# HRT_PDB_17-18_schem.net
KiCad netlist of a schematic drawn in EAGLE
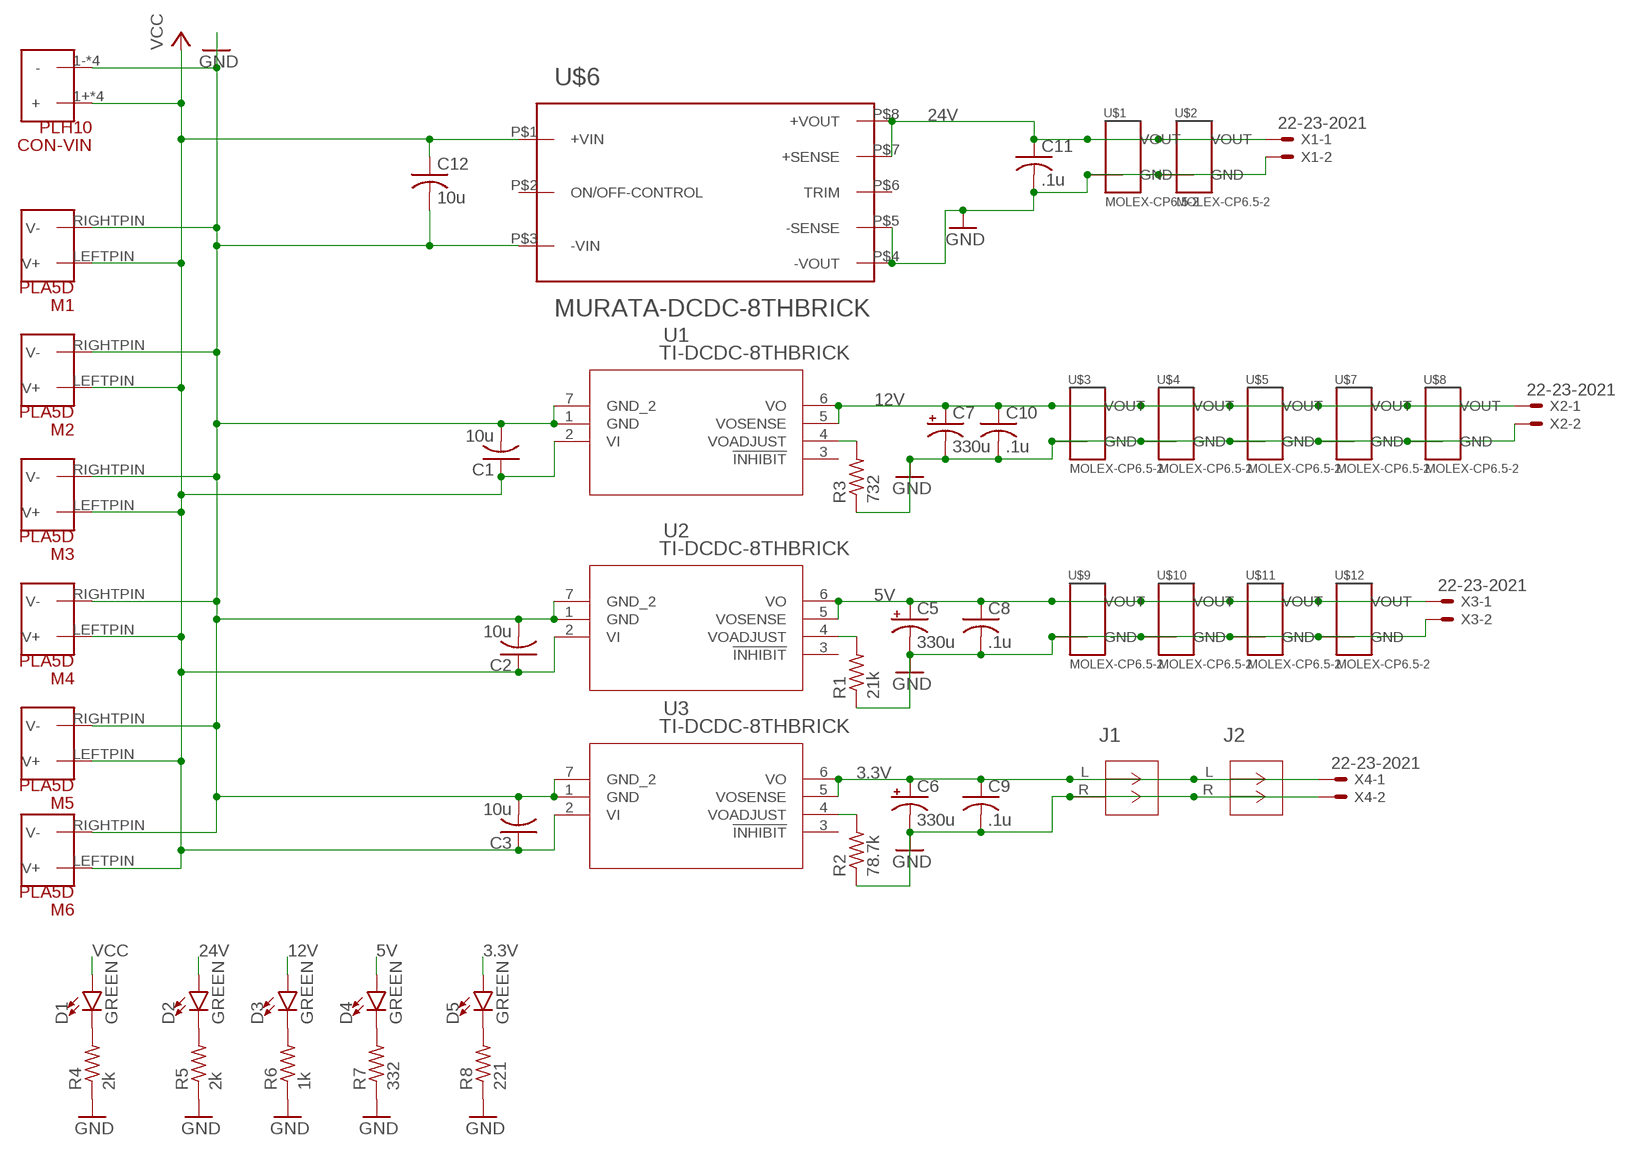
[diagram p0: schematic, sheet 1]

(export (version "E")
  (design (tool "Eeschema 10.0.6"))
  (components
    (comp (ref "C1")
      (value "10u")
      (footprint "eagle-import:C1210")
      (libsource (lib "eagle-import") (part "C-USC1210"))
    )
    (comp (ref "C2")
      (value "10u")
      (footprint "eagle-import:C1210")
      (libsource (lib "eagle-import") (part "C-USC1210"))
    )
    (comp (ref "C3")
      (value "10u")
      (footprint "eagle-import:C1210")
      (libsource (lib "eagle-import") (part "C-USC1210"))
    )
    (comp (ref "C5")
      (value "330u")
      (footprint "eagle-import:E5-10,5")
      (libsource (lib "eagle-import") (part "CPOL-USE5-10.5"))
    )
    (comp (ref "C6")
      (value "330u")
      (footprint "eagle-import:E5-10,5")
      (libsource (lib "eagle-import") (part "CPOL-USE5-10.5"))
    )
    (comp (ref "C7")
      (value "330u")
      (footprint "eagle-import:E5-10,5")
      (libsource (lib "eagle-import") (part "CPOL-USE5-10.5"))
    )
    (comp (ref "C8")
      (value ".1u")
      (footprint "eagle-import:C0603")
      (libsource (lib "eagle-import") (part "C-USC0603"))
    )
    (comp (ref "C9")
      (value ".1u")
      (footprint "eagle-import:C0603")
      (libsource (lib "eagle-import") (part "C-USC0603"))
    )
    (comp (ref "C10")
      (value ".1u")
      (footprint "eagle-import:C0603")
      (libsource (lib "eagle-import") (part "C-USC0603"))
    )
    (comp (ref "C11")
      (value ".1u")
      (footprint "eagle-import:C0603")
      (libsource (lib "eagle-import") (part "C-USC0603"))
    )
    (comp (ref "C12")
      (value "10u")
      (footprint "eagle-import:C1210")
      (libsource (lib "eagle-import") (part "C-USC1210"))
    )
    (comp (ref "CON-VIN")
      (value "PLH10")
      (footprint "eagle-import:PLH10PCKG")
      (libsource (lib "eagle-import") (part "PLH10"))
    )
    (comp (ref "D1")
      (value "GREEN")
      (footprint "eagle-import:LED-0603")
      (libsource (lib "eagle-import") (part "LED-GREEN0603"))
    )
    (comp (ref "D2")
      (value "GREEN")
      (footprint "eagle-import:LED-0603")
      (libsource (lib "eagle-import") (part "LED-GREEN0603"))
    )
    (comp (ref "D3")
      (value "GREEN")
      (footprint "eagle-import:LED-0603")
      (libsource (lib "eagle-import") (part "LED-GREEN0603"))
    )
    (comp (ref "D4")
      (value "GREEN")
      (footprint "eagle-import:LED-0603")
      (libsource (lib "eagle-import") (part "LED-GREEN0603"))
    )
    (comp (ref "D5")
      (value "GREEN")
      (footprint "eagle-import:LED-0603")
      (libsource (lib "eagle-import") (part "LED-GREEN0603"))
    )
    (comp (ref "J1")
      (value "TE-TERM-BLOCK")
      (footprint "eagle-import:TE-TERM-BLOCK")
      (fields (field (name "MANUFACTURER_PART_NUMBER") "2828342"))
      (libsource (lib "eagle-import") (part "TE-TERM-BLOCK"))
    )
    (comp (ref "J2")
      (value "TE-TERM-BLOCK")
      (footprint "eagle-import:TE-TERM-BLOCK")
      (fields (field (name "MANUFACTURER_PART_NUMBER") "2828342"))
      (libsource (lib "eagle-import") (part "TE-TERM-BLOCK"))
    )
    (comp (ref "M1")
      (value "PLA5D")
      (footprint "eagle-import:PLA5PACK")
      (libsource (lib "eagle-import") (part "PLA5D"))
    )
    (comp (ref "M2")
      (value "PLA5D")
      (footprint "eagle-import:PLA5PACK")
      (libsource (lib "eagle-import") (part "PLA5D"))
    )
    (comp (ref "M3")
      (value "PLA5D")
      (footprint "eagle-import:PLA5PACK")
      (libsource (lib "eagle-import") (part "PLA5D"))
    )
    (comp (ref "M4")
      (value "PLA5D")
      (footprint "eagle-import:PLA5PACK")
      (libsource (lib "eagle-import") (part "PLA5D"))
    )
    (comp (ref "M5")
      (value "PLA5D")
      (footprint "eagle-import:PLA5PACK")
      (libsource (lib "eagle-import") (part "PLA5D"))
    )
    (comp (ref "M6")
      (value "PLA5D")
      (footprint "eagle-import:PLA5PACK")
      (libsource (lib "eagle-import") (part "PLA5D"))
    )
    (comp (ref "R1")
      (value "21k")
      (footprint "eagle-import:R0603")
      (libsource (lib "eagle-import") (part "R-US_R0603"))
    )
    (comp (ref "R2")
      (value "78.7k")
      (footprint "eagle-import:R0603")
      (libsource (lib "eagle-import") (part "R-US_R0603"))
    )
    (comp (ref "R3")
      (value "732")
      (footprint "eagle-import:R0603")
      (libsource (lib "eagle-import") (part "R-US_R0603"))
    )
    (comp (ref "R4")
      (value "2k")
      (footprint "eagle-import:R0805")
      (libsource (lib "eagle-import") (part "R-US_R0805"))
    )
    (comp (ref "R5")
      (value "2k")
      (footprint "eagle-import:R0805")
      (libsource (lib "eagle-import") (part "R-US_R0805"))
    )
    (comp (ref "R6")
      (value "1k")
      (footprint "eagle-import:R0805")
      (libsource (lib "eagle-import") (part "R-US_R0805"))
    )
    (comp (ref "R7")
      (value "332")
      (footprint "eagle-import:R0805")
      (libsource (lib "eagle-import") (part "R-US_R0805"))
    )
    (comp (ref "R8")
      (value "221")
      (footprint "eagle-import:R0805")
      (libsource (lib "eagle-import") (part "R-US_R0805"))
    )
    (comp (ref "U$1")
      (value "MOLEX-CP6.5-2")
      (footprint "eagle-import:151048-X2XX")
      (libsource (lib "eagle-import") (part "MOLEX-CP6.5-2"))
    )
    (comp (ref "U$2")
      (value "MOLEX-CP6.5-2")
      (footprint "eagle-import:151048-X2XX")
      (libsource (lib "eagle-import") (part "MOLEX-CP6.5-2"))
    )
    (comp (ref "U$3")
      (value "MOLEX-CP6.5-2")
      (footprint "eagle-import:151048-X2XX")
      (libsource (lib "eagle-import") (part "MOLEX-CP6.5-2"))
    )
    (comp (ref "U$4")
      (value "MOLEX-CP6.5-2")
      (footprint "eagle-import:151048-X2XX")
      (libsource (lib "eagle-import") (part "MOLEX-CP6.5-2"))
    )
    (comp (ref "U$5")
      (value "MOLEX-CP6.5-2")
      (footprint "eagle-import:151048-X2XX")
      (libsource (lib "eagle-import") (part "MOLEX-CP6.5-2"))
    )
    (comp (ref "U$6")
      (value "MURATA-DCDC-8THBRICK")
      (footprint "eagle-import:MURATA-8THBRICK")
      (libsource (lib "eagle-import") (part "MURATA-DCDC-8THBRICK"))
    )
    (comp (ref "U$7")
      (value "MOLEX-CP6.5-2")
      (footprint "eagle-import:151048-X2XX")
      (libsource (lib "eagle-import") (part "MOLEX-CP6.5-2"))
    )
    (comp (ref "U$8")
      (value "MOLEX-CP6.5-2")
      (footprint "eagle-import:151048-X2XX")
      (libsource (lib "eagle-import") (part "MOLEX-CP6.5-2"))
    )
    (comp (ref "U$9")
      (value "MOLEX-CP6.5-2")
      (footprint "eagle-import:151048-X2XX")
      (libsource (lib "eagle-import") (part "MOLEX-CP6.5-2"))
    )
    (comp (ref "U$10")
      (value "MOLEX-CP6.5-2")
      (footprint "eagle-import:151048-X2XX")
      (libsource (lib "eagle-import") (part "MOLEX-CP6.5-2"))
    )
    (comp (ref "U$11")
      (value "MOLEX-CP6.5-2")
      (footprint "eagle-import:151048-X2XX")
      (libsource (lib "eagle-import") (part "MOLEX-CP6.5-2"))
    )
    (comp (ref "U$12")
      (value "MOLEX-CP6.5-2")
      (footprint "eagle-import:151048-X2XX")
      (libsource (lib "eagle-import") (part "MOLEX-CP6.5-2"))
    )
    (comp (ref "U1")
      (value "TI-DCDC-8THBRICK")
      (footprint "eagle-import:TIBRICK")
      (fields (field (name "MANUFACTURER_PART_NUMBER") "PTN78020WAH"))
      (libsource (lib "eagle-import") (part "TI-DCDC-8THBRICK"))
    )
    (comp (ref "U2")
      (value "TI-DCDC-8THBRICK")
      (footprint "eagle-import:TIBRICK")
      (fields (field (name "MANUFACTURER_PART_NUMBER") "PTN78020WAH"))
      (libsource (lib "eagle-import") (part "TI-DCDC-8THBRICK"))
    )
    (comp (ref "U3")
      (value "TI-DCDC-8THBRICK")
      (footprint "eagle-import:TIBRICK")
      (fields (field (name "MANUFACTURER_PART_NUMBER") "PTN78020WAH"))
      (libsource (lib "eagle-import") (part "TI-DCDC-8THBRICK"))
    )
    (comp (ref "X1")
      (value "22-23-2021")
      (footprint "eagle-import:22-23-2021")
      (fields (field (name "MF") "MOLEX"))
      (libsource (lib "eagle-import") (part "22-23-2021"))
    )
    (comp (ref "X2")
      (value "22-23-2021")
      (footprint "eagle-import:22-23-2021")
      (fields (field (name "MF") "MOLEX"))
      (libsource (lib "eagle-import") (part "22-23-2021"))
    )
    (comp (ref "X3")
      (value "22-23-2021")
      (footprint "eagle-import:22-23-2021")
      (fields (field (name "MF") "MOLEX"))
      (libsource (lib "eagle-import") (part "22-23-2021"))
    )
    (comp (ref "X4")
      (value "22-23-2021")
      (footprint "eagle-import:22-23-2021")
      (fields (field (name "MF") "MOLEX"))
      (libsource (lib "eagle-import") (part "22-23-2021"))
    )
  )
  (nets
    (net (code "1") (name "/3.3V") (class "Default")
      (node (ref "C6") (pin "+") (pinfunction "+_+") (pintype "passive"))
      (node (ref "C9") (pin "1") (pinfunction "1_1") (pintype "passive"))
      (node (ref "D5") (pin "A") (pinfunction "A_A") (pintype "passive"))
      (node (ref "J1") (pin "L") (pinfunction "1_L") (pintype "passive"))
      (node (ref "J2") (pin "L") (pinfunction "1_L") (pintype "passive"))
      (node (ref "U3") (pin "5") (pinfunction "VOSENSE_5") (pintype "input"))
      (node (ref "U3") (pin "6") (pinfunction "VO_6") (pintype "input"))
      (node (ref "X4") (pin "1") (pinfunction "S_1") (pintype "passive"))
    )
    (net (code "2") (name "/5V") (class "Default")
      (node (ref "C5") (pin "+") (pinfunction "+_+") (pintype "passive"))
      (node (ref "C8") (pin "1") (pinfunction "1_1") (pintype "passive"))
      (node (ref "D4") (pin "A") (pinfunction "A_A") (pintype "passive"))
      (node (ref "U$10") (pin "VOUT") (pinfunction "VOUT_VOUT") (pintype "bidirectional"))
      (node (ref "U$11") (pin "VOUT") (pinfunction "VOUT_VOUT") (pintype "bidirectional"))
      (node (ref "U$12") (pin "VOUT") (pinfunction "VOUT_VOUT") (pintype "bidirectional"))
      (node (ref "U$9") (pin "VOUT") (pinfunction "VOUT_VOUT") (pintype "bidirectional"))
      (node (ref "U2") (pin "5") (pinfunction "VOSENSE_5") (pintype "input"))
      (node (ref "U2") (pin "6") (pinfunction "VO_6") (pintype "input"))
      (node (ref "X3") (pin "1") (pinfunction "S_1") (pintype "passive"))
    )
    (net (code "3") (name "/12V") (class "Default")
      (node (ref "C10") (pin "1") (pinfunction "1_1") (pintype "passive"))
      (node (ref "C7") (pin "+") (pinfunction "+_+") (pintype "passive"))
      (node (ref "D3") (pin "A") (pinfunction "A_A") (pintype "passive"))
      (node (ref "U$3") (pin "VOUT") (pinfunction "VOUT_VOUT") (pintype "bidirectional"))
      (node (ref "U$4") (pin "VOUT") (pinfunction "VOUT_VOUT") (pintype "bidirectional"))
      (node (ref "U$5") (pin "VOUT") (pinfunction "VOUT_VOUT") (pintype "bidirectional"))
      (node (ref "U$7") (pin "VOUT") (pinfunction "VOUT_VOUT") (pintype "bidirectional"))
      (node (ref "U$8") (pin "VOUT") (pinfunction "VOUT_VOUT") (pintype "bidirectional"))
      (node (ref "U1") (pin "5") (pinfunction "VOSENSE_5") (pintype "input"))
      (node (ref "U1") (pin "6") (pinfunction "VO_6") (pintype "input"))
      (node (ref "X2") (pin "1") (pinfunction "S_1") (pintype "passive"))
    )
    (net (code "4") (name "/24V") (class "Default")
      (node (ref "C11") (pin "1") (pinfunction "1_1") (pintype "passive"))
      (node (ref "D2") (pin "A") (pinfunction "A_A") (pintype "passive"))
      (node (ref "U$1") (pin "VOUT") (pinfunction "VOUT_VOUT") (pintype "bidirectional"))
      (node (ref "U$2") (pin "VOUT") (pinfunction "VOUT_VOUT") (pintype "bidirectional"))
      (node (ref "U$6") (pin "P$7") (pinfunction "+SENSE_P$7") (pintype "bidirectional"))
      (node (ref "U$6") (pin "P$8") (pinfunction "+VOUT_P$8") (pintype "bidirectional"))
      (node (ref "X1") (pin "1") (pinfunction "S_1") (pintype "passive"))
    )
    (net (code "5") (name "GND") (class "Default")
      (node (ref "C1") (pin "2") (pinfunction "2_2") (pintype "passive"))
      (node (ref "C10") (pin "2") (pinfunction "2_2") (pintype "passive"))
      (node (ref "C11") (pin "2") (pinfunction "2_2") (pintype "passive"))
      (node (ref "C12") (pin "2") (pinfunction "2_2") (pintype "passive"))
      (node (ref "C2") (pin "2") (pinfunction "2_2") (pintype "passive"))
      (node (ref "C3") (pin "2") (pinfunction "2_2") (pintype "passive"))
      (node (ref "C5") (pin "-") (pinfunction "-_-") (pintype "passive"))
      (node (ref "C6") (pin "-") (pinfunction "-_-") (pintype "passive"))
      (node (ref "C7") (pin "-") (pinfunction "-_-") (pintype "passive"))
      (node (ref "C8") (pin "2") (pinfunction "2_2") (pintype "passive"))
      (node (ref "C9") (pin "2") (pinfunction "2_2") (pintype "passive"))
      (node (ref "CON-VIN") (pin "1-") (pinfunction "-_1-") (pintype "bidirectional"))
      (node (ref "CON-VIN") (pin "2-") (pinfunction "-_2-") (pintype "bidirectional"))
      (node (ref "CON-VIN") (pin "3-") (pinfunction "-_3-") (pintype "bidirectional"))
      (node (ref "CON-VIN") (pin "4-") (pinfunction "-_4-") (pintype "bidirectional"))
      (node (ref "J1") (pin "R") (pinfunction "2_R") (pintype "passive"))
      (node (ref "J2") (pin "R") (pinfunction "2_R") (pintype "passive"))
      (node (ref "M1") (pin "RIGHTPIN") (pinfunction "V-_RIGHTPIN") (pintype "bidirectional"))
      (node (ref "M2") (pin "RIGHTPIN") (pinfunction "V-_RIGHTPIN") (pintype "bidirectional"))
      (node (ref "M3") (pin "RIGHTPIN") (pinfunction "V-_RIGHTPIN") (pintype "bidirectional"))
      (node (ref "M4") (pin "RIGHTPIN") (pinfunction "V-_RIGHTPIN") (pintype "bidirectional"))
      (node (ref "M5") (pin "RIGHTPIN") (pinfunction "V-_RIGHTPIN") (pintype "bidirectional"))
      (node (ref "M6") (pin "RIGHTPIN") (pinfunction "V-_RIGHTPIN") (pintype "bidirectional"))
      (node (ref "R1") (pin "1") (pinfunction "1_1") (pintype "passive"))
      (node (ref "R2") (pin "1") (pinfunction "1_1") (pintype "passive"))
      (node (ref "R3") (pin "1") (pinfunction "1_1") (pintype "passive"))
      (node (ref "R4") (pin "1") (pinfunction "1_1") (pintype "passive"))
      (node (ref "R5") (pin "1") (pinfunction "1_1") (pintype "passive"))
      (node (ref "R6") (pin "1") (pinfunction "1_1") (pintype "passive"))
      (node (ref "R7") (pin "1") (pinfunction "1_1") (pintype "passive"))
      (node (ref "R8") (pin "1") (pinfunction "1_1") (pintype "passive"))
      (node (ref "U$1") (pin "GND") (pinfunction "GND_GND") (pintype "bidirectional"))
      (node (ref "U$10") (pin "GND") (pinfunction "GND_GND") (pintype "bidirectional"))
      (node (ref "U$11") (pin "GND") (pinfunction "GND_GND") (pintype "bidirectional"))
      (node (ref "U$12") (pin "GND") (pinfunction "GND_GND") (pintype "bidirectional"))
      (node (ref "U$2") (pin "GND") (pinfunction "GND_GND") (pintype "bidirectional"))
      (node (ref "U$3") (pin "GND") (pinfunction "GND_GND") (pintype "bidirectional"))
      (node (ref "U$4") (pin "GND") (pinfunction "GND_GND") (pintype "bidirectional"))
      (node (ref "U$5") (pin "GND") (pinfunction "GND_GND") (pintype "bidirectional"))
      (node (ref "U$6") (pin "P$3") (pinfunction "-VIN_P$3") (pintype "bidirectional"))
      (node (ref "U$6") (pin "P$4") (pinfunction "-VOUT_P$4") (pintype "bidirectional"))
      (node (ref "U$6") (pin "P$5") (pinfunction "-SENSE_P$5") (pintype "bidirectional"))
      (node (ref "U$7") (pin "GND") (pinfunction "GND_GND") (pintype "bidirectional"))
      (node (ref "U$8") (pin "GND") (pinfunction "GND_GND") (pintype "bidirectional"))
      (node (ref "U$9") (pin "GND") (pinfunction "GND_GND") (pintype "bidirectional"))
      (node (ref "U1") (pin "1") (pinfunction "GND_1") (pintype "power_in"))
      (node (ref "U1") (pin "7") (pinfunction "GND_2_7") (pintype "power_in"))
      (node (ref "U2") (pin "1") (pinfunction "GND_1") (pintype "power_in"))
      (node (ref "U2") (pin "7") (pinfunction "GND_2_7") (pintype "power_in"))
      (node (ref "U3") (pin "1") (pinfunction "GND_1") (pintype "power_in"))
      (node (ref "U3") (pin "7") (pinfunction "GND_2_7") (pintype "power_in"))
      (node (ref "X1") (pin "2") (pinfunction "S_2") (pintype "passive"))
      (node (ref "X2") (pin "2") (pinfunction "S_2") (pintype "passive"))
      (node (ref "X3") (pin "2") (pinfunction "S_2") (pintype "passive"))
      (node (ref "X4") (pin "2") (pinfunction "S_2") (pintype "passive"))
    )
    (net (code "6") (name "Net-(D1-PadC)") (class "Default")
      (node (ref "D1") (pin "C") (pinfunction "C_C") (pintype "passive"))
      (node (ref "R4") (pin "2") (pinfunction "2_2") (pintype "passive"))
    )
    (net (code "7") (name "Net-(D2-PadC)") (class "Default")
      (node (ref "D2") (pin "C") (pinfunction "C_C") (pintype "passive"))
      (node (ref "R5") (pin "2") (pinfunction "2_2") (pintype "passive"))
    )
    (net (code "8") (name "Net-(D3-PadC)") (class "Default")
      (node (ref "D3") (pin "C") (pinfunction "C_C") (pintype "passive"))
      (node (ref "R6") (pin "2") (pinfunction "2_2") (pintype "passive"))
    )
    (net (code "9") (name "Net-(D4-PadC)") (class "Default")
      (node (ref "D4") (pin "C") (pinfunction "C_C") (pintype "passive"))
      (node (ref "R7") (pin "2") (pinfunction "2_2") (pintype "passive"))
    )
    (net (code "10") (name "Net-(D5-PadC)") (class "Default")
      (node (ref "D5") (pin "C") (pinfunction "C_C") (pintype "passive"))
      (node (ref "R8") (pin "2") (pinfunction "2_2") (pintype "passive"))
    )
    (net (code "11") (name "Net-(U1-VOADJUST)") (class "Default")
      (node (ref "R3") (pin "2") (pinfunction "2_2") (pintype "passive"))
      (node (ref "U1") (pin "4") (pinfunction "VOADJUST_4") (pintype "input"))
    )
    (net (code "12") (name "Net-(U2-VOADJUST)") (class "Default")
      (node (ref "R1") (pin "2") (pinfunction "2_2") (pintype "passive"))
      (node (ref "U2") (pin "4") (pinfunction "VOADJUST_4") (pintype "input"))
    )
    (net (code "13") (name "Net-(U3-VOADJUST)") (class "Default")
      (node (ref "R2") (pin "2") (pinfunction "2_2") (pintype "passive"))
      (node (ref "U3") (pin "4") (pinfunction "VOADJUST_4") (pintype "input"))
    )
    (net (code "14") (name "VCC") (class "Default")
      (node (ref "C1") (pin "1") (pinfunction "1_1") (pintype "passive"))
      (node (ref "C12") (pin "1") (pinfunction "1_1") (pintype "passive"))
      (node (ref "C2") (pin "1") (pinfunction "1_1") (pintype "passive"))
      (node (ref "C3") (pin "1") (pinfunction "1_1") (pintype "passive"))
      (node (ref "CON-VIN") (pin "1+") (pinfunction "+_1+") (pintype "bidirectional"))
      (node (ref "CON-VIN") (pin "2+") (pinfunction "+_2+") (pintype "bidirectional"))
      (node (ref "CON-VIN") (pin "3+") (pinfunction "+_3+") (pintype "bidirectional"))
      (node (ref "CON-VIN") (pin "4+") (pinfunction "+_4+") (pintype "bidirectional"))
      (node (ref "D1") (pin "A") (pinfunction "A_A") (pintype "passive"))
      (node (ref "M1") (pin "LEFTPIN") (pinfunction "V+_LEFTPIN") (pintype "bidirectional"))
      (node (ref "M2") (pin "LEFTPIN") (pinfunction "V+_LEFTPIN") (pintype "bidirectional"))
      (node (ref "M3") (pin "LEFTPIN") (pinfunction "V+_LEFTPIN") (pintype "bidirectional"))
      (node (ref "M4") (pin "LEFTPIN") (pinfunction "V+_LEFTPIN") (pintype "bidirectional"))
      (node (ref "M5") (pin "LEFTPIN") (pinfunction "V+_LEFTPIN") (pintype "bidirectional"))
      (node (ref "M6") (pin "LEFTPIN") (pinfunction "V+_LEFTPIN") (pintype "bidirectional"))
      (node (ref "U$6") (pin "P$1") (pinfunction "+VIN_P$1") (pintype "bidirectional"))
      (node (ref "U1") (pin "2") (pinfunction "VI_2") (pintype "input"))
      (node (ref "U2") (pin "2") (pinfunction "VI_2") (pintype "input"))
      (node (ref "U3") (pin "2") (pinfunction "VI_2") (pintype "input"))
    )
    (net (code "15") (name "unconnected-(U$6-ON{slash}OFF-CONTROL-PadP$2)") (class "Default")
      (node (ref "U$6") (pin "P$2") (pinfunction "ON/OFF-CONTROL_P$2") (pintype "bidirectional"))
    )
    (net (code "16") (name "unconnected-(U$6-TRIM-PadP$6)") (class "Default")
      (node (ref "U$6") (pin "P$6") (pinfunction "TRIM_P$6") (pintype "bidirectional"))
    )
    (net (code "17") (name "unconnected-(U1-~{INHIBIT}-Pad3)") (class "Default")
      (node (ref "U1") (pin "3") (pinfunction "~{INHIBIT}_3") (pintype "input"))
    )
    (net (code "18") (name "unconnected-(U2-~{INHIBIT}-Pad3)") (class "Default")
      (node (ref "U2") (pin "3") (pinfunction "~{INHIBIT}_3") (pintype "input"))
    )
    (net (code "19") (name "unconnected-(U3-~{INHIBIT}-Pad3)") (class "Default")
      (node (ref "U3") (pin "3") (pinfunction "~{INHIBIT}_3") (pintype "input"))
    )
  )
)
